# top.net
KiCad netlist of a schematic drawn in Altium Designer
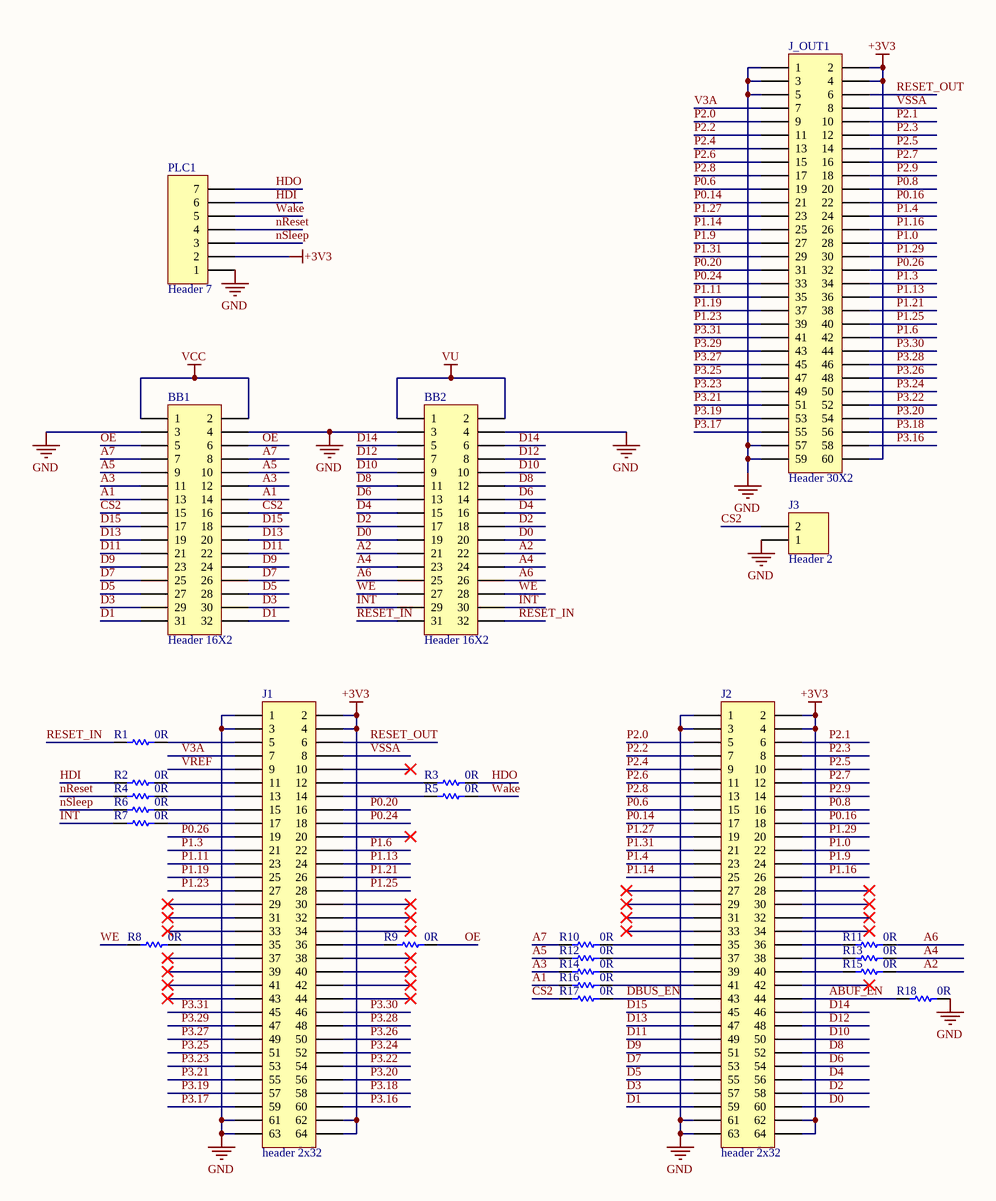
[diagram p0: top.SchDoc]

(export (version "E")
  (design (tool "Eeschema 10.0.6"))
  (components
    (comp (ref "BB1")
      (value "Header 16X2")
      (footprint "HDR2X16")
      (description "Header, 16-Pin, Dual row")
      (fields (field (name "PUBLISHER") "Altium Limited"))
      (libsource (lib "Miscellaneous Connectors") (part "Header 16X2"))
    )
    (comp (ref "BB2")
      (value "Header 16X2")
      (footprint "HDR2X16")
      (description "Header, 16-Pin, Dual row")
      (fields (field (name "PUBLISHER") "Altium Limited"))
      (libsource (lib "Miscellaneous Connectors") (part "Header 16X2"))
    )
    (comp (ref "J1")
      (value "header 2x32")
      (footprint "HDR2X32_special")
      (libsource (lib "new_library") (part "header 2x32"))
    )
    (comp (ref "J2")
      (value "header 2x32")
      (footprint "HDR2X32_special")
      (libsource (lib "new_library") (part "header 2x32"))
    )
    (comp (ref "J3")
      (value "Header 2")
      (footprint "HDR1X2")
      (description "Header, 2-Pin")
      (fields (field (name "PUBLISHER") "Altium Limited"))
      (libsource (lib "Miscellaneous Connectors") (part "Header 2"))
    )
    (comp (ref "J_OUT1")
      (value "Header 30X2")
      (footprint "HDR2X30")
      (description "Header, 30-Pin, Dual row")
      (fields (field (name "PUBLISHER") "Altium Limited"))
      (libsource (lib "Miscellaneous Connectors") (part "Header 30X2"))
    )
    (comp (ref "PLC1")
      (value "Header 7")
      (footprint "HDR1X7")
      (description "Header, 7-Pin")
      (fields (field (name "PUBLISHER") "Altium Limited"))
      (libsource (lib "Miscellaneous Connectors") (part "Header 7"))
    )
    (comp (ref "R1")
      (value "0R")
      (footprint "6-0805_L")
      (description "Resistor")
      (fields (field (name "Comment") "Res1") (field (name "PUBLISHER") "Altium Limited"))
      (libsource (lib "Miscellaneous Devices") (part "Res1"))
    )
    (comp (ref "R2")
      (value "0R")
      (footprint "6-0805_L")
      (description "Resistor")
      (fields (field (name "Comment") "Res1") (field (name "PUBLISHER") "Altium Limited"))
      (libsource (lib "Miscellaneous Devices") (part "Res1"))
    )
    (comp (ref "R3")
      (value "0R")
      (footprint "6-0805_L")
      (description "Resistor")
      (fields (field (name "Comment") "Res1") (field (name "PUBLISHER") "Altium Limited"))
      (libsource (lib "Miscellaneous Devices") (part "Res1"))
    )
    (comp (ref "R4")
      (value "0R")
      (footprint "6-0805_L")
      (description "Resistor")
      (fields (field (name "Comment") "Res1") (field (name "PUBLISHER") "Altium Limited"))
      (libsource (lib "Miscellaneous Devices") (part "Res1"))
    )
    (comp (ref "R5")
      (value "0R")
      (footprint "6-0805_L")
      (description "Resistor")
      (fields (field (name "Comment") "Res1") (field (name "PUBLISHER") "Altium Limited"))
      (libsource (lib "Miscellaneous Devices") (part "Res1"))
    )
    (comp (ref "R6")
      (value "0R")
      (footprint "6-0805_L")
      (description "Resistor")
      (fields (field (name "Comment") "Res1") (field (name "PUBLISHER") "Altium Limited"))
      (libsource (lib "Miscellaneous Devices") (part "Res1"))
    )
    (comp (ref "R7")
      (value "0R")
      (footprint "6-0805_L")
      (description "Resistor")
      (fields (field (name "Comment") "Res1") (field (name "PUBLISHER") "Altium Limited"))
      (libsource (lib "Miscellaneous Devices") (part "Res1"))
    )
    (comp (ref "R8")
      (value "0R")
      (footprint "6-0805_L")
      (description "Resistor")
      (fields (field (name "Comment") "Res1") (field (name "PUBLISHER") "Altium Limited"))
      (libsource (lib "Miscellaneous Devices") (part "Res1"))
    )
    (comp (ref "R9")
      (value "0R")
      (footprint "6-0805_L")
      (description "Resistor")
      (fields (field (name "Comment") "Res1") (field (name "PUBLISHER") "Altium Limited"))
      (libsource (lib "Miscellaneous Devices") (part "Res1"))
    )
    (comp (ref "R10")
      (value "0R")
      (footprint "6-0805_L")
      (description "Resistor")
      (fields (field (name "Comment") "Res1") (field (name "PUBLISHER") "Altium Limited"))
      (libsource (lib "Miscellaneous Devices") (part "Res1"))
    )
    (comp (ref "R11")
      (value "0R")
      (footprint "6-0805_L")
      (description "Resistor")
      (fields (field (name "Comment") "Res1") (field (name "PUBLISHER") "Altium Limited"))
      (libsource (lib "Miscellaneous Devices") (part "Res1"))
    )
    (comp (ref "R12")
      (value "0R")
      (footprint "6-0805_L")
      (description "Resistor")
      (fields (field (name "Comment") "Res1") (field (name "PUBLISHER") "Altium Limited"))
      (libsource (lib "Miscellaneous Devices") (part "Res1"))
    )
    (comp (ref "R13")
      (value "0R")
      (footprint "6-0805_L")
      (description "Resistor")
      (fields (field (name "Comment") "Res1") (field (name "PUBLISHER") "Altium Limited"))
      (libsource (lib "Miscellaneous Devices") (part "Res1"))
    )
    (comp (ref "R14")
      (value "0R")
      (footprint "6-0805_L")
      (description "Resistor")
      (fields (field (name "Comment") "Res1") (field (name "PUBLISHER") "Altium Limited"))
      (libsource (lib "Miscellaneous Devices") (part "Res1"))
    )
    (comp (ref "R15")
      (value "0R")
      (footprint "6-0805_L")
      (description "Resistor")
      (fields (field (name "Comment") "Res1") (field (name "PUBLISHER") "Altium Limited"))
      (libsource (lib "Miscellaneous Devices") (part "Res1"))
    )
    (comp (ref "R16")
      (value "0R")
      (footprint "6-0805_L")
      (description "Resistor")
      (fields (field (name "Comment") "Res1") (field (name "PUBLISHER") "Altium Limited"))
      (libsource (lib "Miscellaneous Devices") (part "Res1"))
    )
    (comp (ref "R17")
      (value "0R")
      (footprint "6-0805_L")
      (description "Resistor")
      (fields (field (name "Comment") "Res1") (field (name "PUBLISHER") "Altium Limited"))
      (libsource (lib "Miscellaneous Devices") (part "Res1"))
    )
    (comp (ref "R18")
      (value "0R")
      (footprint "6-0805_L")
      (description "Resistor")
      (fields (field (name "Comment") "Res1") (field (name "PUBLISHER") "Altium Limited"))
      (libsource (lib "Miscellaneous Devices") (part "Res1"))
    )
  )
  (nets
    (net (code "1") (name "+3V3") (class "Default")
      (node (ref "J1") (pin "2") (pinfunction "2_2") (pintype "passive"))
      (node (ref "J1") (pin "4") (pinfunction "4_4") (pintype "passive"))
      (node (ref "J1") (pin "62") (pinfunction "62_62") (pintype "passive"))
      (node (ref "J1") (pin "64") (pinfunction "64_64") (pintype "passive"))
      (node (ref "J2") (pin "2") (pinfunction "2_2") (pintype "passive"))
      (node (ref "J2") (pin "4") (pinfunction "4_4") (pintype "passive"))
      (node (ref "J2") (pin "62") (pinfunction "62_62") (pintype "passive"))
      (node (ref "J2") (pin "64") (pinfunction "64_64") (pintype "passive"))
      (node (ref "J_OUT1") (pin "2") (pinfunction "2_2") (pintype "passive"))
      (node (ref "J_OUT1") (pin "4") (pinfunction "4_4") (pintype "passive"))
      (node (ref "J_OUT1") (pin "60") (pinfunction "60_60") (pintype "passive"))
      (node (ref "PLC1") (pin "2") (pinfunction "2_2") (pintype "passive"))
    )
    (net (code "2") (name "/A1") (class "Default")
      (node (ref "BB1") (pin "13") (pinfunction "13_13") (pintype "passive"))
      (node (ref "BB1") (pin "14") (pinfunction "14_14") (pintype "passive"))
      (node (ref "R16") (pin "1") (pinfunction "1_1") (pintype "passive"))
    )
    (net (code "3") (name "/A2") (class "Default")
      (node (ref "BB2") (pin "21") (pinfunction "21_21") (pintype "passive"))
      (node (ref "BB2") (pin "22") (pinfunction "22_22") (pintype "passive"))
      (node (ref "R15") (pin "2") (pinfunction "2_2") (pintype "passive"))
    )
    (net (code "4") (name "/A3") (class "Default")
      (node (ref "BB1") (pin "11") (pinfunction "11_11") (pintype "passive"))
      (node (ref "BB1") (pin "12") (pinfunction "12_12") (pintype "passive"))
      (node (ref "R14") (pin "1") (pinfunction "1_1") (pintype "passive"))
    )
    (net (code "5") (name "/A4") (class "Default")
      (node (ref "BB2") (pin "23") (pinfunction "23_23") (pintype "passive"))
      (node (ref "BB2") (pin "24") (pinfunction "24_24") (pintype "passive"))
      (node (ref "R13") (pin "2") (pinfunction "2_2") (pintype "passive"))
    )
    (net (code "6") (name "/A5") (class "Default")
      (node (ref "BB1") (pin "10") (pinfunction "10_10") (pintype "passive"))
      (node (ref "BB1") (pin "9") (pinfunction "9_9") (pintype "passive"))
      (node (ref "R12") (pin "1") (pinfunction "1_1") (pintype "passive"))
    )
    (net (code "7") (name "/A6") (class "Default")
      (node (ref "BB2") (pin "25") (pinfunction "25_25") (pintype "passive"))
      (node (ref "BB2") (pin "26") (pinfunction "26_26") (pintype "passive"))
      (node (ref "R11") (pin "2") (pinfunction "2_2") (pintype "passive"))
    )
    (net (code "8") (name "/A7") (class "Default")
      (node (ref "BB1") (pin "7") (pinfunction "7_7") (pintype "passive"))
      (node (ref "BB1") (pin "8") (pinfunction "8_8") (pintype "passive"))
      (node (ref "R10") (pin "1") (pinfunction "1_1") (pintype "passive"))
    )
    (net (code "9") (name "/ABUF_EN") (class "Default")
      (node (ref "J2") (pin "44") (pinfunction "44_44") (pintype "passive"))
      (node (ref "R18") (pin "1") (pinfunction "1_1") (pintype "passive"))
    )
    (net (code "10") (name "/CS2") (class "Default")
      (node (ref "BB1") (pin "15") (pinfunction "15_15") (pintype "passive"))
      (node (ref "BB1") (pin "16") (pinfunction "16_16") (pintype "passive"))
      (node (ref "J3") (pin "2") (pinfunction "2_2") (pintype "passive"))
      (node (ref "R17") (pin "1") (pinfunction "1_1") (pintype "passive"))
    )
    (net (code "11") (name "/D0") (class "Default")
      (node (ref "BB2") (pin "19") (pinfunction "19_19") (pintype "passive"))
      (node (ref "BB2") (pin "20") (pinfunction "20_20") (pintype "passive"))
      (node (ref "J2") (pin "60") (pinfunction "60_60") (pintype "passive"))
    )
    (net (code "12") (name "/D1") (class "Default")
      (node (ref "BB1") (pin "31") (pinfunction "31_31") (pintype "passive"))
      (node (ref "BB1") (pin "32") (pinfunction "32_32") (pintype "passive"))
      (node (ref "J2") (pin "59") (pinfunction "59_59") (pintype "passive"))
    )
    (net (code "13") (name "/D2") (class "Default")
      (node (ref "BB2") (pin "17") (pinfunction "17_17") (pintype "passive"))
      (node (ref "BB2") (pin "18") (pinfunction "18_18") (pintype "passive"))
      (node (ref "J2") (pin "58") (pinfunction "58_58") (pintype "passive"))
    )
    (net (code "14") (name "/D3") (class "Default")
      (node (ref "BB1") (pin "29") (pinfunction "29_29") (pintype "passive"))
      (node (ref "BB1") (pin "30") (pinfunction "30_30") (pintype "passive"))
      (node (ref "J2") (pin "57") (pinfunction "57_57") (pintype "passive"))
    )
    (net (code "15") (name "/D4") (class "Default")
      (node (ref "BB2") (pin "15") (pinfunction "15_15") (pintype "passive"))
      (node (ref "BB2") (pin "16") (pinfunction "16_16") (pintype "passive"))
      (node (ref "J2") (pin "56") (pinfunction "56_56") (pintype "passive"))
    )
    (net (code "16") (name "/D5") (class "Default")
      (node (ref "BB1") (pin "27") (pinfunction "27_27") (pintype "passive"))
      (node (ref "BB1") (pin "28") (pinfunction "28_28") (pintype "passive"))
      (node (ref "J2") (pin "55") (pinfunction "55_55") (pintype "passive"))
    )
    (net (code "17") (name "/D6") (class "Default")
      (node (ref "BB2") (pin "13") (pinfunction "13_13") (pintype "passive"))
      (node (ref "BB2") (pin "14") (pinfunction "14_14") (pintype "passive"))
      (node (ref "J2") (pin "54") (pinfunction "54_54") (pintype "passive"))
    )
    (net (code "18") (name "/D7") (class "Default")
      (node (ref "BB1") (pin "25") (pinfunction "25_25") (pintype "passive"))
      (node (ref "BB1") (pin "26") (pinfunction "26_26") (pintype "passive"))
      (node (ref "J2") (pin "53") (pinfunction "53_53") (pintype "passive"))
    )
    (net (code "19") (name "/D8") (class "Default")
      (node (ref "BB2") (pin "11") (pinfunction "11_11") (pintype "passive"))
      (node (ref "BB2") (pin "12") (pinfunction "12_12") (pintype "passive"))
      (node (ref "J2") (pin "52") (pinfunction "52_52") (pintype "passive"))
    )
    (net (code "20") (name "/D9") (class "Default")
      (node (ref "BB1") (pin "23") (pinfunction "23_23") (pintype "passive"))
      (node (ref "BB1") (pin "24") (pinfunction "24_24") (pintype "passive"))
      (node (ref "J2") (pin "51") (pinfunction "51_51") (pintype "passive"))
    )
    (net (code "21") (name "/D10") (class "Default")
      (node (ref "BB2") (pin "10") (pinfunction "10_10") (pintype "passive"))
      (node (ref "BB2") (pin "9") (pinfunction "9_9") (pintype "passive"))
      (node (ref "J2") (pin "50") (pinfunction "50_50") (pintype "passive"))
    )
    (net (code "22") (name "/D11") (class "Default")
      (node (ref "BB1") (pin "21") (pinfunction "21_21") (pintype "passive"))
      (node (ref "BB1") (pin "22") (pinfunction "22_22") (pintype "passive"))
      (node (ref "J2") (pin "49") (pinfunction "49_49") (pintype "passive"))
    )
    (net (code "23") (name "/D12") (class "Default")
      (node (ref "BB2") (pin "7") (pinfunction "7_7") (pintype "passive"))
      (node (ref "BB2") (pin "8") (pinfunction "8_8") (pintype "passive"))
      (node (ref "J2") (pin "48") (pinfunction "48_48") (pintype "passive"))
    )
    (net (code "24") (name "/D13") (class "Default")
      (node (ref "BB1") (pin "19") (pinfunction "19_19") (pintype "passive"))
      (node (ref "BB1") (pin "20") (pinfunction "20_20") (pintype "passive"))
      (node (ref "J2") (pin "47") (pinfunction "47_47") (pintype "passive"))
    )
    (net (code "25") (name "/D14") (class "Default")
      (node (ref "BB2") (pin "5") (pinfunction "5_5") (pintype "passive"))
      (node (ref "BB2") (pin "6") (pinfunction "6_6") (pintype "passive"))
      (node (ref "J2") (pin "46") (pinfunction "46_46") (pintype "passive"))
    )
    (net (code "26") (name "/D15") (class "Default")
      (node (ref "BB1") (pin "17") (pinfunction "17_17") (pintype "passive"))
      (node (ref "BB1") (pin "18") (pinfunction "18_18") (pintype "passive"))
      (node (ref "J2") (pin "45") (pinfunction "45_45") (pintype "passive"))
    )
    (net (code "27") (name "/DBUS_EN") (class "Default")
      (node (ref "J2") (pin "43") (pinfunction "43_43") (pintype "passive"))
      (node (ref "R17") (pin "2") (pinfunction "2_2") (pintype "passive"))
    )
    (net (code "28") (name "/HDI") (class "Default")
      (node (ref "PLC1") (pin "6") (pinfunction "6_6") (pintype "passive"))
      (node (ref "R2") (pin "1") (pinfunction "1_1") (pintype "passive"))
    )
    (net (code "29") (name "/HDO") (class "Default")
      (node (ref "PLC1") (pin "7") (pinfunction "7_7") (pintype "passive"))
      (node (ref "R3") (pin "2") (pinfunction "2_2") (pintype "passive"))
    )
    (net (code "30") (name "/INT") (class "Default")
      (node (ref "BB2") (pin "29") (pinfunction "29_29") (pintype "passive"))
      (node (ref "BB2") (pin "30") (pinfunction "30_30") (pintype "passive"))
      (node (ref "R7") (pin "1") (pinfunction "1_1") (pintype "passive"))
    )
    (net (code "31") (name "/OE") (class "Default")
      (node (ref "BB1") (pin "5") (pinfunction "5_5") (pintype "passive"))
      (node (ref "BB1") (pin "6") (pinfunction "6_6") (pintype "passive"))
      (node (ref "R9") (pin "2") (pinfunction "2_2") (pintype "passive"))
    )
    (net (code "32") (name "/P0.6") (class "Default")
      (node (ref "J2") (pin "15") (pinfunction "15_15") (pintype "passive"))
      (node (ref "J_OUT1") (pin "19") (pinfunction "19_19") (pintype "passive"))
    )
    (net (code "33") (name "/P0.8") (class "Default")
      (node (ref "J2") (pin "16") (pinfunction "16_16") (pintype "passive"))
      (node (ref "J_OUT1") (pin "20") (pinfunction "20_20") (pintype "passive"))
    )
    (net (code "34") (name "/P0.14") (class "Default")
      (node (ref "J2") (pin "17") (pinfunction "17_17") (pintype "passive"))
      (node (ref "J_OUT1") (pin "21") (pinfunction "21_21") (pintype "passive"))
    )
    (net (code "35") (name "/P0.16") (class "Default")
      (node (ref "J2") (pin "18") (pinfunction "18_18") (pintype "passive"))
      (node (ref "J_OUT1") (pin "22") (pinfunction "22_22") (pintype "passive"))
    )
    (net (code "36") (name "/P0.20") (class "Default")
      (node (ref "J1") (pin "16") (pinfunction "16_16") (pintype "passive"))
      (node (ref "J_OUT1") (pin "31") (pinfunction "31_31") (pintype "passive"))
    )
    (net (code "37") (name "/P0.24") (class "Default")
      (node (ref "J1") (pin "18") (pinfunction "18_18") (pintype "passive"))
      (node (ref "J_OUT1") (pin "33") (pinfunction "33_33") (pintype "passive"))
    )
    (net (code "38") (name "/P0.26") (class "Default")
      (node (ref "J1") (pin "19") (pinfunction "19_19") (pintype "passive"))
      (node (ref "J_OUT1") (pin "32") (pinfunction "32_32") (pintype "passive"))
    )
    (net (code "39") (name "/P1.0") (class "Default")
      (node (ref "J2") (pin "22") (pinfunction "22_22") (pintype "passive"))
      (node (ref "J_OUT1") (pin "28") (pinfunction "28_28") (pintype "passive"))
    )
    (net (code "40") (name "/P1.3") (class "Default")
      (node (ref "J1") (pin "21") (pinfunction "21_21") (pintype "passive"))
      (node (ref "J_OUT1") (pin "34") (pinfunction "34_34") (pintype "passive"))
    )
    (net (code "41") (name "/P1.4") (class "Default")
      (node (ref "J2") (pin "23") (pinfunction "23_23") (pintype "passive"))
      (node (ref "J_OUT1") (pin "24") (pinfunction "24_24") (pintype "passive"))
    )
    (net (code "42") (name "/P1.6") (class "Default")
      (node (ref "J1") (pin "22") (pinfunction "22_22") (pintype "passive"))
      (node (ref "J_OUT1") (pin "42") (pinfunction "42_42") (pintype "passive"))
    )
    (net (code "43") (name "/P1.9") (class "Default")
      (node (ref "J2") (pin "24") (pinfunction "24_24") (pintype "passive"))
      (node (ref "J_OUT1") (pin "27") (pinfunction "27_27") (pintype "passive"))
    )
    (net (code "44") (name "/P1.11") (class "Default")
      (node (ref "J1") (pin "23") (pinfunction "23_23") (pintype "passive"))
      (node (ref "J_OUT1") (pin "35") (pinfunction "35_35") (pintype "passive"))
    )
    (net (code "45") (name "/P1.13") (class "Default")
      (node (ref "J1") (pin "24") (pinfunction "24_24") (pintype "passive"))
      (node (ref "J_OUT1") (pin "36") (pinfunction "36_36") (pintype "passive"))
    )
    (net (code "46") (name "/P1.14") (class "Default")
      (node (ref "J2") (pin "25") (pinfunction "25_25") (pintype "passive"))
      (node (ref "J_OUT1") (pin "25") (pinfunction "25_25") (pintype "passive"))
    )
    (net (code "47") (name "/P1.16") (class "Default")
      (node (ref "J2") (pin "26") (pinfunction "26_26") (pintype "passive"))
      (node (ref "J_OUT1") (pin "26") (pinfunction "26_26") (pintype "passive"))
    )
    (net (code "48") (name "/P1.19") (class "Default")
      (node (ref "J1") (pin "25") (pinfunction "25_25") (pintype "passive"))
      (node (ref "J_OUT1") (pin "37") (pinfunction "37_37") (pintype "passive"))
    )
    (net (code "49") (name "/P1.21") (class "Default")
      (node (ref "J1") (pin "26") (pinfunction "26_26") (pintype "passive"))
      (node (ref "J_OUT1") (pin "38") (pinfunction "38_38") (pintype "passive"))
    )
    (net (code "50") (name "/P1.23") (class "Default")
      (node (ref "J1") (pin "27") (pinfunction "27_27") (pintype "passive"))
      (node (ref "J_OUT1") (pin "39") (pinfunction "39_39") (pintype "passive"))
    )
    (net (code "51") (name "/P1.25") (class "Default")
      (node (ref "J1") (pin "28") (pinfunction "28_28") (pintype "passive"))
      (node (ref "J_OUT1") (pin "40") (pinfunction "40_40") (pintype "passive"))
    )
    (net (code "52") (name "/P1.27") (class "Default")
      (node (ref "J2") (pin "19") (pinfunction "19_19") (pintype "passive"))
      (node (ref "J_OUT1") (pin "23") (pinfunction "23_23") (pintype "passive"))
    )
    (net (code "53") (name "/P1.29") (class "Default")
      (node (ref "J2") (pin "20") (pinfunction "20_20") (pintype "passive"))
      (node (ref "J_OUT1") (pin "30") (pinfunction "30_30") (pintype "passive"))
    )
    (net (code "54") (name "/P1.31") (class "Default")
      (node (ref "J2") (pin "21") (pinfunction "21_21") (pintype "passive"))
      (node (ref "J_OUT1") (pin "29") (pinfunction "29_29") (pintype "passive"))
    )
    (net (code "55") (name "/P2.0") (class "Default")
      (node (ref "J2") (pin "5") (pinfunction "5_5") (pintype "passive"))
      (node (ref "J_OUT1") (pin "9") (pinfunction "9_9") (pintype "passive"))
    )
    (net (code "56") (name "/P2.1") (class "Default")
      (node (ref "J2") (pin "6") (pinfunction "6_6") (pintype "passive"))
      (node (ref "J_OUT1") (pin "10") (pinfunction "10_10") (pintype "passive"))
    )
    (net (code "57") (name "/P2.2") (class "Default")
      (node (ref "J2") (pin "7") (pinfunction "7_7") (pintype "passive"))
      (node (ref "J_OUT1") (pin "11") (pinfunction "11_11") (pintype "passive"))
    )
    (net (code "58") (name "/P2.3") (class "Default")
      (node (ref "J2") (pin "8") (pinfunction "8_8") (pintype "passive"))
      (node (ref "J_OUT1") (pin "12") (pinfunction "12_12") (pintype "passive"))
    )
    (net (code "59") (name "/P2.4") (class "Default")
      (node (ref "J2") (pin "9") (pinfunction "9_9") (pintype "passive"))
      (node (ref "J_OUT1") (pin "13") (pinfunction "13_13") (pintype "passive"))
    )
    (net (code "60") (name "/P2.5") (class "Default")
      (node (ref "J2") (pin "10") (pinfunction "10_10") (pintype "passive"))
      (node (ref "J_OUT1") (pin "14") (pinfunction "14_14") (pintype "passive"))
    )
    (net (code "61") (name "/P2.6") (class "Default")
      (node (ref "J2") (pin "11") (pinfunction "11_11") (pintype "passive"))
      (node (ref "J_OUT1") (pin "15") (pinfunction "15_15") (pintype "passive"))
    )
    (net (code "62") (name "/P2.7") (class "Default")
      (node (ref "J2") (pin "12") (pinfunction "12_12") (pintype "passive"))
      (node (ref "J_OUT1") (pin "16") (pinfunction "16_16") (pintype "passive"))
    )
    (net (code "63") (name "/P2.8") (class "Default")
      (node (ref "J2") (pin "13") (pinfunction "13_13") (pintype "passive"))
      (node (ref "J_OUT1") (pin "17") (pinfunction "17_17") (pintype "passive"))
    )
    (net (code "64") (name "/P2.9") (class "Default")
      (node (ref "J2") (pin "14") (pinfunction "14_14") (pintype "passive"))
      (node (ref "J_OUT1") (pin "18") (pinfunction "18_18") (pintype "passive"))
    )
    (net (code "65") (name "/P3.16") (class "Default")
      (node (ref "J1") (pin "60") (pinfunction "60_60") (pintype "passive"))
      (node (ref "J_OUT1") (pin "58") (pinfunction "58_58") (pintype "passive"))
    )
    (net (code "66") (name "/P3.17") (class "Default")
      (node (ref "J1") (pin "59") (pinfunction "59_59") (pintype "passive"))
      (node (ref "J_OUT1") (pin "55") (pinfunction "55_55") (pintype "passive"))
    )
    (net (code "67") (name "/P3.18") (class "Default")
      (node (ref "J1") (pin "58") (pinfunction "58_58") (pintype "passive"))
      (node (ref "J_OUT1") (pin "56") (pinfunction "56_56") (pintype "passive"))
    )
    (net (code "68") (name "/P3.19") (class "Default")
      (node (ref "J1") (pin "57") (pinfunction "57_57") (pintype "passive"))
      (node (ref "J_OUT1") (pin "53") (pinfunction "53_53") (pintype "passive"))
    )
    (net (code "69") (name "/P3.20") (class "Default")
      (node (ref "J1") (pin "56") (pinfunction "56_56") (pintype "passive"))
      (node (ref "J_OUT1") (pin "54") (pinfunction "54_54") (pintype "passive"))
    )
    (net (code "70") (name "/P3.21") (class "Default")
      (node (ref "J1") (pin "55") (pinfunction "55_55") (pintype "passive"))
      (node (ref "J_OUT1") (pin "51") (pinfunction "51_51") (pintype "passive"))
    )
    (net (code "71") (name "/P3.22") (class "Default")
      (node (ref "J1") (pin "54") (pinfunction "54_54") (pintype "passive"))
      (node (ref "J_OUT1") (pin "52") (pinfunction "52_52") (pintype "passive"))
    )
    (net (code "72") (name "/P3.23") (class "Default")
      (node (ref "J1") (pin "53") (pinfunction "53_53") (pintype "passive"))
      (node (ref "J_OUT1") (pin "49") (pinfunction "49_49") (pintype "passive"))
    )
    (net (code "73") (name "/P3.24") (class "Default")
      (node (ref "J1") (pin "52") (pinfunction "52_52") (pintype "passive"))
      (node (ref "J_OUT1") (pin "50") (pinfunction "50_50") (pintype "passive"))
    )
    (net (code "74") (name "/P3.25") (class "Default")
      (node (ref "J1") (pin "51") (pinfunction "51_51") (pintype "passive"))
      (node (ref "J_OUT1") (pin "47") (pinfunction "47_47") (pintype "passive"))
    )
    (net (code "75") (name "/P3.26") (class "Default")
      (node (ref "J1") (pin "50") (pinfunction "50_50") (pintype "passive"))
      (node (ref "J_OUT1") (pin "48") (pinfunction "48_48") (pintype "passive"))
    )
    (net (code "76") (name "/P3.27") (class "Default")
      (node (ref "J1") (pin "49") (pinfunction "49_49") (pintype "passive"))
      (node (ref "J_OUT1") (pin "45") (pinfunction "45_45") (pintype "passive"))
    )
    (net (code "77") (name "/P3.28") (class "Default")
      (node (ref "J1") (pin "48") (pinfunction "48_48") (pintype "passive"))
      (node (ref "J_OUT1") (pin "46") (pinfunction "46_46") (pintype "passive"))
    )
    (net (code "78") (name "/P3.29") (class "Default")
      (node (ref "J1") (pin "47") (pinfunction "47_47") (pintype "passive"))
      (node (ref "J_OUT1") (pin "43") (pinfunction "43_43") (pintype "passive"))
    )
    (net (code "79") (name "/P3.30") (class "Default")
      (node (ref "J1") (pin "46") (pinfunction "46_46") (pintype "passive"))
      (node (ref "J_OUT1") (pin "44") (pinfunction "44_44") (pintype "passive"))
    )
    (net (code "80") (name "/P3.31") (class "Default")
      (node (ref "J1") (pin "45") (pinfunction "45_45") (pintype "passive"))
      (node (ref "J_OUT1") (pin "41") (pinfunction "41_41") (pintype "passive"))
    )
    (net (code "81") (name "/RESET_IN") (class "Default")
      (node (ref "BB2") (pin "31") (pinfunction "31_31") (pintype "passive"))
      (node (ref "BB2") (pin "32") (pinfunction "32_32") (pintype "passive"))
      (node (ref "R1") (pin "1") (pinfunction "1_1") (pintype "passive"))
    )
    (net (code "82") (name "/RESET_OUT") (class "Default")
      (node (ref "J1") (pin "6") (pinfunction "6_6") (pintype "passive"))
      (node (ref "J_OUT1") (pin "6") (pinfunction "6_6") (pintype "passive"))
    )
    (net (code "83") (name "/V3A") (class "Default")
      (node (ref "J1") (pin "7") (pinfunction "7_7") (pintype "passive"))
      (node (ref "J_OUT1") (pin "7") (pinfunction "7_7") (pintype "passive"))
    )
    (net (code "84") (name "/VREF") (class "Default")
      (node (ref "J1") (pin "9") (pinfunction "9_9") (pintype "passive"))
    )
    (net (code "85") (name "/VSSA") (class "Default")
      (node (ref "J1") (pin "8") (pinfunction "8_8") (pintype "passive"))
      (node (ref "J_OUT1") (pin "8") (pinfunction "8_8") (pintype "passive"))
    )
    (net (code "86") (name "/WE") (class "Default")
      (node (ref "BB2") (pin "27") (pinfunction "27_27") (pintype "passive"))
      (node (ref "BB2") (pin "28") (pinfunction "28_28") (pintype "passive"))
      (node (ref "R8") (pin "1") (pinfunction "1_1") (pintype "passive"))
    )
    (net (code "87") (name "/Wake") (class "Default")
      (node (ref "PLC1") (pin "5") (pinfunction "5_5") (pintype "passive"))
      (node (ref "R5") (pin "2") (pinfunction "2_2") (pintype "passive"))
    )
    (net (code "88") (name "/nReset") (class "Default")
      (node (ref "PLC1") (pin "4") (pinfunction "4_4") (pintype "passive"))
      (node (ref "R4") (pin "1") (pinfunction "1_1") (pintype "passive"))
    )
    (net (code "89") (name "/nSleep") (class "Default")
      (node (ref "PLC1") (pin "3") (pinfunction "3_3") (pintype "passive"))
      (node (ref "R6") (pin "1") (pinfunction "1_1") (pintype "passive"))
    )
    (net (code "90") (name "GND") (class "Default")
      (node (ref "BB1") (pin "3") (pinfunction "3_3") (pintype "passive"))
      (node (ref "BB1") (pin "4") (pinfunction "4_4") (pintype "passive"))
      (node (ref "BB2") (pin "3") (pinfunction "3_3") (pintype "passive"))
      (node (ref "BB2") (pin "4") (pinfunction "4_4") (pintype "passive"))
      (node (ref "J1") (pin "1") (pinfunction "1_1") (pintype "passive"))
      (node (ref "J1") (pin "3") (pinfunction "3_3") (pintype "passive"))
      (node (ref "J1") (pin "61") (pinfunction "61_61") (pintype "passive"))
      (node (ref "J1") (pin "63") (pinfunction "63_63") (pintype "passive"))
      (node (ref "J2") (pin "1") (pinfunction "1_1") (pintype "passive"))
      (node (ref "J2") (pin "3") (pinfunction "3_3") (pintype "passive"))
      (node (ref "J2") (pin "61") (pinfunction "61_61") (pintype "passive"))
      (node (ref "J2") (pin "63") (pinfunction "63_63") (pintype "passive"))
      (node (ref "J3") (pin "1") (pinfunction "1_1") (pintype "passive"))
      (node (ref "J_OUT1") (pin "1") (pinfunction "1_1") (pintype "passive"))
      (node (ref "J_OUT1") (pin "3") (pinfunction "3_3") (pintype "passive"))
      (node (ref "J_OUT1") (pin "5") (pinfunction "5_5") (pintype "passive"))
      (node (ref "J_OUT1") (pin "57") (pinfunction "57_57") (pintype "passive"))
      (node (ref "J_OUT1") (pin "59") (pinfunction "59_59") (pintype "passive"))
      (node (ref "PLC1") (pin "1") (pinfunction "1_1") (pintype "passive"))
      (node (ref "R18") (pin "2") (pinfunction "2_2") (pintype "passive"))
    )
    (net (code "91") (name "Net-(J1-Pad5)") (class "Default")
      (node (ref "J1") (pin "5") (pinfunction "5_5") (pintype "passive"))
      (node (ref "R1") (pin "2") (pinfunction "2_2") (pintype "passive"))
    )
    (net (code "92") (name "Net-(J1-Pad11)") (class "Default")
      (node (ref "J1") (pin "11") (pinfunction "11_11") (pintype "passive"))
      (node (ref "R2") (pin "2") (pinfunction "2_2") (pintype "passive"))
    )
    (net (code "93") (name "Net-(J1-Pad12)") (class "Default")
      (node (ref "J1") (pin "12") (pinfunction "12_12") (pintype "passive"))
      (node (ref "R3") (pin "1") (pinfunction "1_1") (pintype "passive"))
    )
    (net (code "94") (name "Net-(J1-Pad13)") (class "Default")
      (node (ref "J1") (pin "13") (pinfunction "13_13") (pintype "passive"))
      (node (ref "R4") (pin "2") (pinfunction "2_2") (pintype "passive"))
    )
    (net (code "95") (name "Net-(J1-Pad14)") (class "Default")
      (node (ref "J1") (pin "14") (pinfunction "14_14") (pintype "passive"))
      (node (ref "R5") (pin "1") (pinfunction "1_1") (pintype "passive"))
    )
    (net (code "96") (name "Net-(J1-Pad15)") (class "Default")
      (node (ref "J1") (pin "15") (pinfunction "15_15") (pintype "passive"))
      (node (ref "R6") (pin "2") (pinfunction "2_2") (pintype "passive"))
    )
    (net (code "97") (name "Net-(J1-Pad17)") (class "Default")
      (node (ref "J1") (pin "17") (pinfunction "17_17") (pintype "passive"))
      (node (ref "R7") (pin "2") (pinfunction "2_2") (pintype "passive"))
    )
    (net (code "98") (name "Net-(J1-Pad35)") (class "Default")
      (node (ref "J1") (pin "35") (pinfunction "35_35") (pintype "passive"))
      (node (ref "R8") (pin "2") (pinfunction "2_2") (pintype "passive"))
    )
    (net (code "99") (name "Net-(J1-Pad36)") (class "Default")
      (node (ref "J1") (pin "36") (pinfunction "36_36") (pintype "passive"))
      (node (ref "R9") (pin "1") (pinfunction "1_1") (pintype "passive"))
    )
    (net (code "100") (name "Net-(J2-Pad35)") (class "Default")
      (node (ref "J2") (pin "35") (pinfunction "35_35") (pintype "passive"))
      (node (ref "R10") (pin "2") (pinfunction "2_2") (pintype "passive"))
    )
    (net (code "101") (name "Net-(J2-Pad36)") (class "Default")
      (node (ref "J2") (pin "36") (pinfunction "36_36") (pintype "passive"))
      (node (ref "R11") (pin "1") (pinfunction "1_1") (pintype "passive"))
    )
    (net (code "102") (name "Net-(J2-Pad37)") (class "Default")
      (node (ref "J2") (pin "37") (pinfunction "37_37") (pintype "passive"))
      (node (ref "R12") (pin "2") (pinfunction "2_2") (pintype "passive"))
    )
    (net (code "103") (name "Net-(J2-Pad38)") (class "Default")
      (node (ref "J2") (pin "38") (pinfunction "38_38") (pintype "passive"))
      (node (ref "R13") (pin "1") (pinfunction "1_1") (pintype "passive"))
    )
    (net (code "104") (name "Net-(J2-Pad39)") (class "Default")
      (node (ref "J2") (pin "39") (pinfunction "39_39") (pintype "passive"))
      (node (ref "R14") (pin "2") (pinfunction "2_2") (pintype "passive"))
    )
    (net (code "105") (name "Net-(J2-Pad40)") (class "Default")
      (node (ref "J2") (pin "40") (pinfunction "40_40") (pintype "passive"))
      (node (ref "R15") (pin "1") (pinfunction "1_1") (pintype "passive"))
    )
    (net (code "106") (name "Net-(J2-Pad41)") (class "Default")
      (node (ref "J2") (pin "41") (pinfunction "41_41") (pintype "passive"))
      (node (ref "R16") (pin "2") (pinfunction "2_2") (pintype "passive"))
    )
    (net (code "107") (name "VCC") (class "Default")
      (node (ref "BB1") (pin "1") (pinfunction "1_1") (pintype "passive"))
      (node (ref "BB1") (pin "2") (pinfunction "2_2") (pintype "passive"))
    )
    (net (code "108") (name "VU") (class "Default")
      (node (ref "BB2") (pin "1") (pinfunction "1_1") (pintype "passive"))
      (node (ref "BB2") (pin "2") (pinfunction "2_2") (pintype "passive"))
    )
    (net (code "109") (name "unconnected-(J1-Pad10)") (class "Default")
      (node (ref "J1") (pin "10") (pinfunction "10_10") (pintype "passive+no_connect"))
    )
    (net (code "110") (name "unconnected-(J1-Pad20)") (class "Default")
      (node (ref "J1") (pin "20") (pinfunction "20_20") (pintype "passive+no_connect"))
    )
    (net (code "111") (name "unconnected-(J1-Pad29)") (class "Default")
      (node (ref "J1") (pin "29") (pinfunction "29_29") (pintype "passive+no_connect"))
    )
    (net (code "112") (name "unconnected-(J1-Pad30)") (class "Default")
      (node (ref "J1") (pin "30") (pinfunction "30_30") (pintype "passive+no_connect"))
    )
    (net (code "113") (name "unconnected-(J1-Pad31)") (class "Default")
      (node (ref "J1") (pin "31") (pinfunction "31_31") (pintype "passive+no_connect"))
    )
    (net (code "114") (name "unconnected-(J1-Pad32)") (class "Default")
      (node (ref "J1") (pin "32") (pinfunction "32_32") (pintype "passive+no_connect"))
    )
    (net (code "115") (name "unconnected-(J1-Pad33)") (class "Default")
      (node (ref "J1") (pin "33") (pinfunction "33_33") (pintype "passive+no_connect"))
    )
    (net (code "116") (name "unconnected-(J1-Pad34)") (class "Default")
      (node (ref "J1") (pin "34") (pinfunction "34_34") (pintype "passive+no_connect"))
    )
    (net (code "117") (name "unconnected-(J1-Pad37)") (class "Default")
      (node (ref "J1") (pin "37") (pinfunction "37_37") (pintype "passive+no_connect"))
    )
    (net (code "118") (name "unconnected-(J1-Pad38)") (class "Default")
      (node (ref "J1") (pin "38") (pinfunction "38_38") (pintype "passive+no_connect"))
    )
    (net (code "119") (name "unconnected-(J1-Pad39)") (class "Default")
      (node (ref "J1") (pin "39") (pinfunction "39_39") (pintype "passive+no_connect"))
    )
    (net (code "120") (name "unconnected-(J1-Pad40)") (class "Default")
      (node (ref "J1") (pin "40") (pinfunction "40_40") (pintype "passive+no_connect"))
    )
    (net (code "121") (name "unconnected-(J1-Pad41)") (class "Default")
      (node (ref "J1") (pin "41") (pinfunction "41_41") (pintype "passive+no_connect"))
    )
    (net (code "122") (name "unconnected-(J1-Pad42)") (class "Default")
      (node (ref "J1") (pin "42") (pinfunction "42_42") (pintype "passive+no_connect"))
    )
    (net (code "123") (name "unconnected-(J1-Pad43)") (class "Default")
      (node (ref "J1") (pin "43") (pinfunction "43_43") (pintype "passive+no_connect"))
    )
    (net (code "124") (name "unconnected-(J1-Pad44)") (class "Default")
      (node (ref "J1") (pin "44") (pinfunction "44_44") (pintype "passive+no_connect"))
    )
    (net (code "125") (name "unconnected-(J2-Pad27)") (class "Default")
      (node (ref "J2") (pin "27") (pinfunction "27_27") (pintype "passive+no_connect"))
    )
    (net (code "126") (name "unconnected-(J2-Pad28)") (class "Default")
      (node (ref "J2") (pin "28") (pinfunction "28_28") (pintype "passive+no_connect"))
    )
    (net (code "127") (name "unconnected-(J2-Pad29)") (class "Default")
      (node (ref "J2") (pin "29") (pinfunction "29_29") (pintype "passive+no_connect"))
    )
    (net (code "128") (name "unconnected-(J2-Pad30)") (class "Default")
      (node (ref "J2") (pin "30") (pinfunction "30_30") (pintype "passive+no_connect"))
    )
    (net (code "129") (name "unconnected-(J2-Pad31)") (class "Default")
      (node (ref "J2") (pin "31") (pinfunction "31_31") (pintype "passive+no_connect"))
    )
    (net (code "130") (name "unconnected-(J2-Pad32)") (class "Default")
      (node (ref "J2") (pin "32") (pinfunction "32_32") (pintype "passive+no_connect"))
    )
    (net (code "131") (name "unconnected-(J2-Pad33)") (class "Default")
      (node (ref "J2") (pin "33") (pinfunction "33_33") (pintype "passive+no_connect"))
    )
    (net (code "132") (name "unconnected-(J2-Pad34)") (class "Default")
      (node (ref "J2") (pin "34") (pinfunction "34_34") (pintype "passive+no_connect"))
    )
    (net (code "133") (name "unconnected-(J2-Pad42)") (class "Default")
      (node (ref "J2") (pin "42") (pinfunction "42_42") (pintype "passive+no_connect"))
    )
  )
)
